# badge.net
KiCad netlist of a schematic drawn in EAGLE
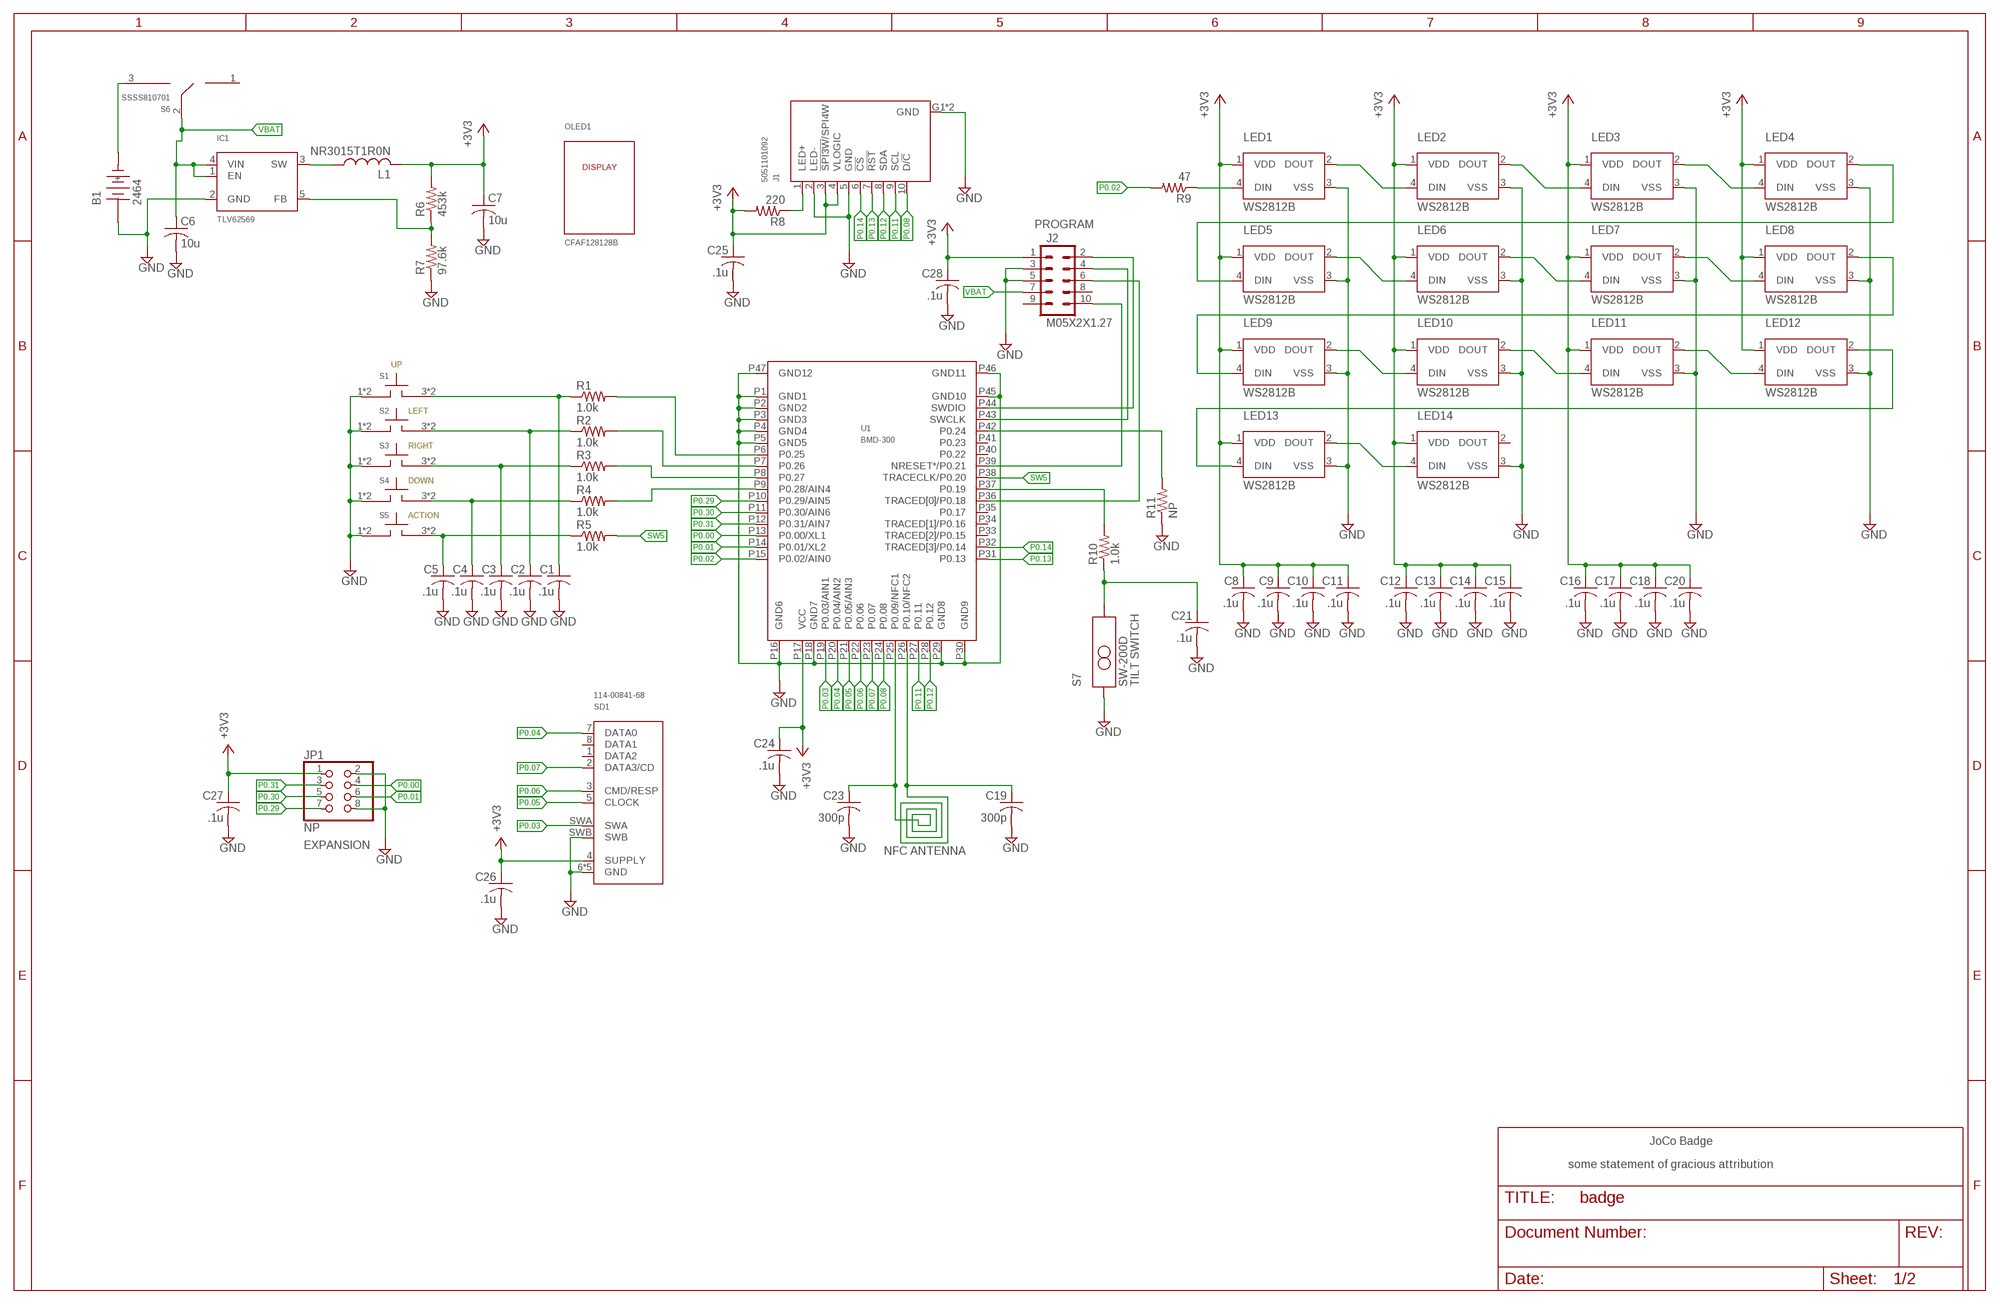
[diagram p0: schematic, sheet 1]
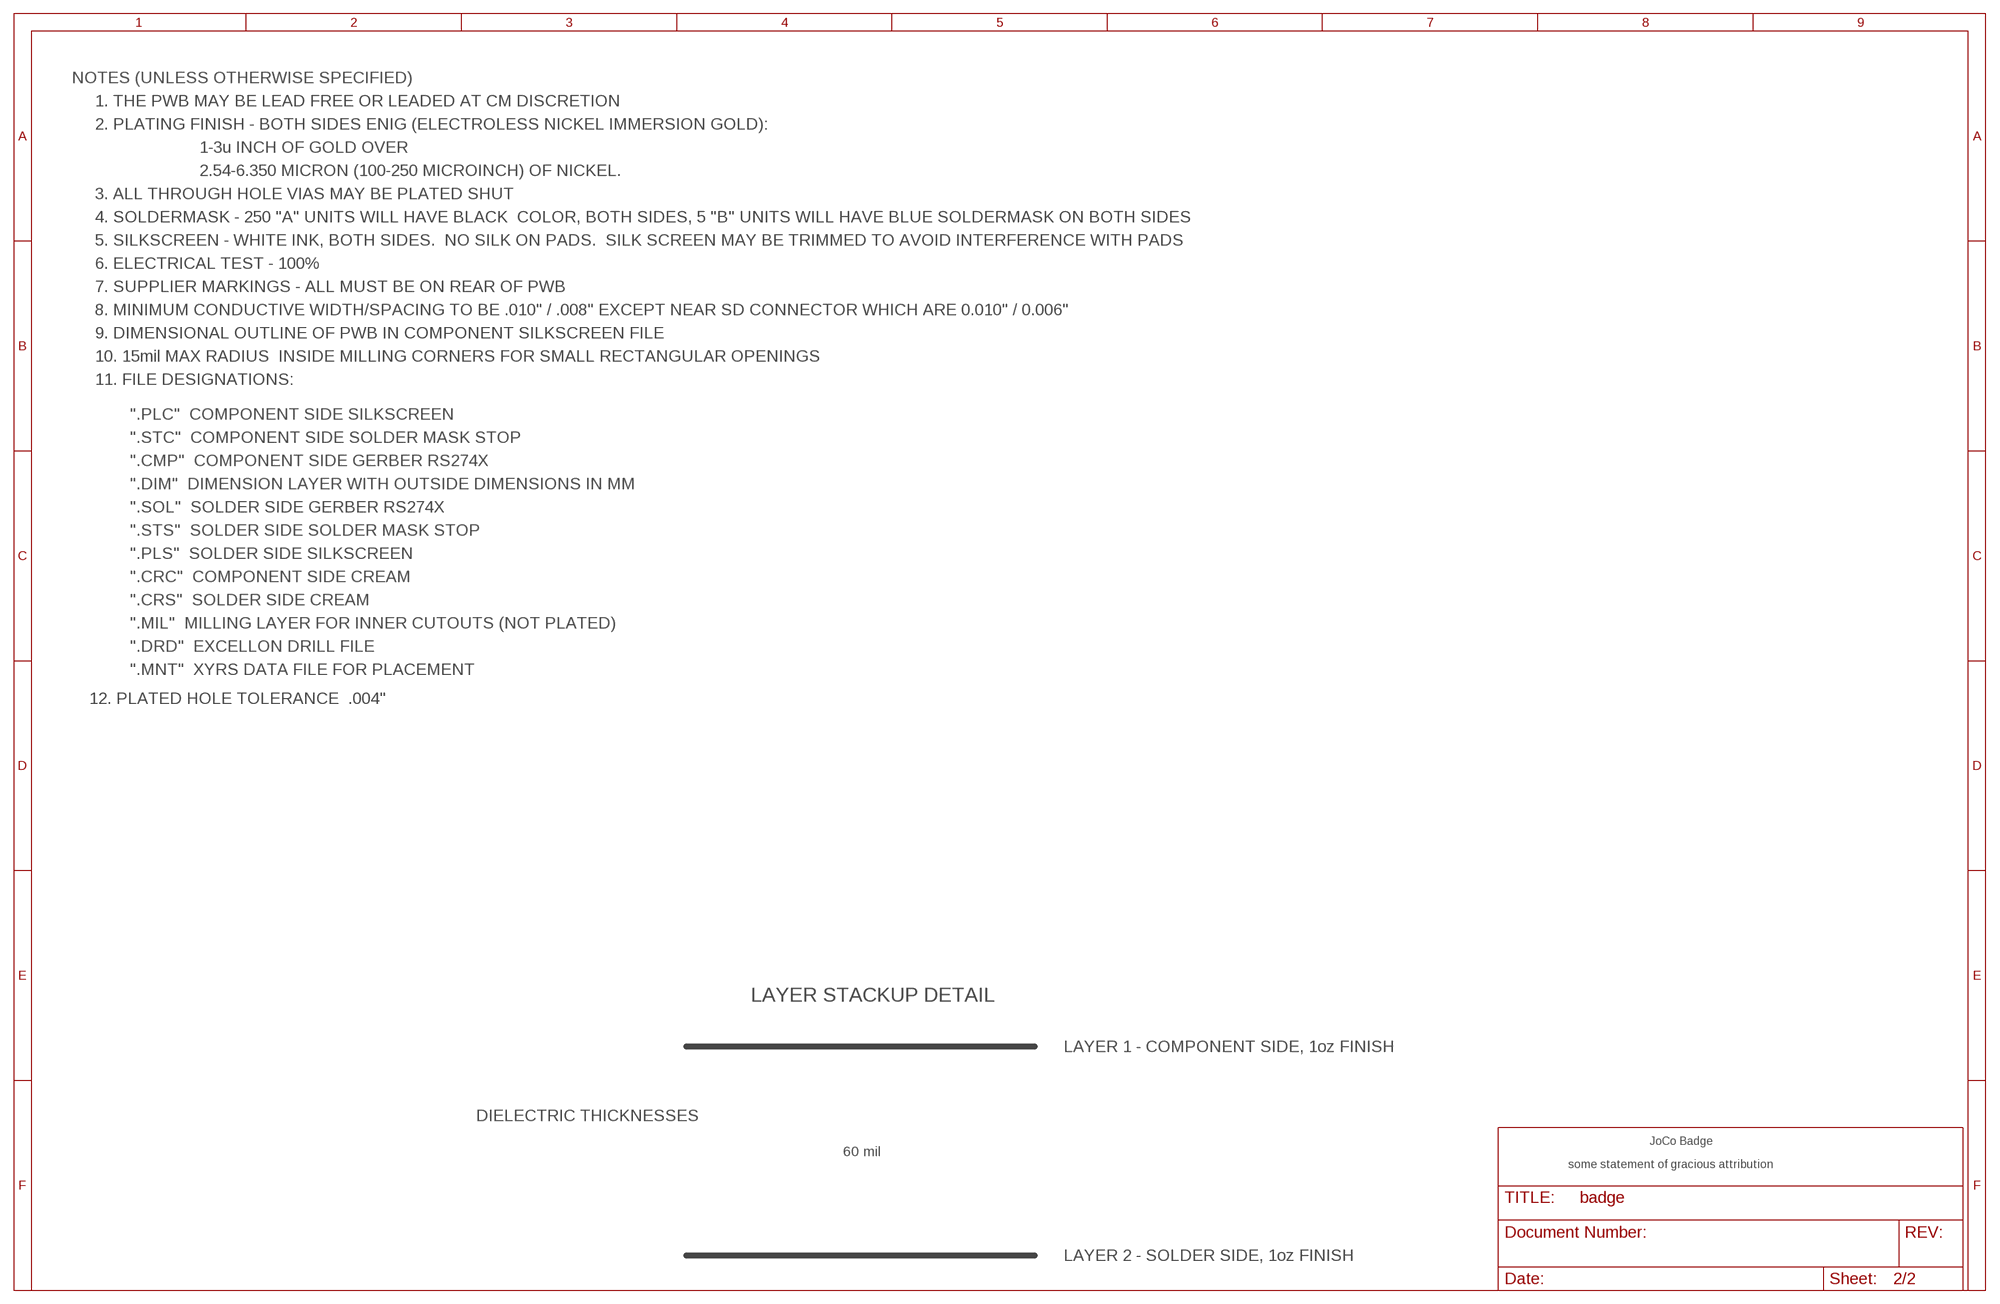
[diagram p1: schematic, sheet 2]

(export (version "E")
  (design (tool "Eeschema 10.0.6"))
  (components
    (comp (ref "B1")
      (value "2464")
      (footprint "eagle-import:2464")
      (libsource (lib "eagle-import") (part "2464"))
    )
    (comp (ref "C1")
      (value ".1u")
      (footprint "eagle-import:C0402K")
      (libsource (lib "eagle-import") (part "C-USC0402K"))
    )
    (comp (ref "C2")
      (value ".1u")
      (footprint "eagle-import:C0402K")
      (libsource (lib "eagle-import") (part "C-USC0402K"))
    )
    (comp (ref "C3")
      (value ".1u")
      (footprint "eagle-import:C0402K")
      (libsource (lib "eagle-import") (part "C-USC0402K"))
    )
    (comp (ref "C4")
      (value ".1u")
      (footprint "eagle-import:C0402K")
      (libsource (lib "eagle-import") (part "C-USC0402K"))
    )
    (comp (ref "C5")
      (value ".1u")
      (footprint "eagle-import:C0402K")
      (libsource (lib "eagle-import") (part "C-USC0402K"))
    )
    (comp (ref "C6")
      (value "10u")
      (footprint "eagle-import:C0805K")
      (fields (field (name "MPN") "JMK212BJ106KD-T"))
      (libsource (lib "eagle-import") (part "C-USC0805K"))
    )
    (comp (ref "C7")
      (value "10u")
      (footprint "eagle-import:C0805K")
      (fields (field (name "MPN") "JMK212BJ106KD-T"))
      (libsource (lib "eagle-import") (part "C-USC0805K"))
    )
    (comp (ref "C8")
      (value ".1u")
      (footprint "eagle-import:C0402K")
      (libsource (lib "eagle-import") (part "C-USC0402K"))
    )
    (comp (ref "C9")
      (value ".1u")
      (footprint "eagle-import:C0402K")
      (libsource (lib "eagle-import") (part "C-USC0402K"))
    )
    (comp (ref "C10")
      (value ".1u")
      (footprint "eagle-import:C0402K")
      (libsource (lib "eagle-import") (part "C-USC0402K"))
    )
    (comp (ref "C11")
      (value ".1u")
      (footprint "eagle-import:C0402K")
      (libsource (lib "eagle-import") (part "C-USC0402K"))
    )
    (comp (ref "C12")
      (value ".1u")
      (footprint "eagle-import:C0402K")
      (libsource (lib "eagle-import") (part "C-USC0402K"))
    )
    (comp (ref "C13")
      (value ".1u")
      (footprint "eagle-import:C0402K")
      (libsource (lib "eagle-import") (part "C-USC0402K"))
    )
    (comp (ref "C14")
      (value ".1u")
      (footprint "eagle-import:C0402K")
      (libsource (lib "eagle-import") (part "C-USC0402K"))
    )
    (comp (ref "C15")
      (value ".1u")
      (footprint "eagle-import:C0402K")
      (libsource (lib "eagle-import") (part "C-USC0402K"))
    )
    (comp (ref "C16")
      (value ".1u")
      (footprint "eagle-import:C0402K")
      (libsource (lib "eagle-import") (part "C-USC0402K"))
    )
    (comp (ref "C17")
      (value ".1u")
      (footprint "eagle-import:C0402K")
      (libsource (lib "eagle-import") (part "C-USC0402K"))
    )
    (comp (ref "C18")
      (value ".1u")
      (footprint "eagle-import:C0402K")
      (libsource (lib "eagle-import") (part "C-USC0402K"))
    )
    (comp (ref "C19")
      (value "300p")
      (footprint "eagle-import:C0603K")
      (libsource (lib "eagle-import") (part "C-USC0603K"))
    )
    (comp (ref "C20")
      (value ".1u")
      (footprint "eagle-import:C0402K")
      (libsource (lib "eagle-import") (part "C-USC0402K"))
    )
    (comp (ref "C21")
      (value ".1u")
      (footprint "eagle-import:C0402K")
      (libsource (lib "eagle-import") (part "C-USC0402K"))
    )
    (comp (ref "C23")
      (value "300p")
      (footprint "eagle-import:C0603K")
      (libsource (lib "eagle-import") (part "C-USC0603K"))
    )
    (comp (ref "C24")
      (value ".1u")
      (footprint "eagle-import:C0402K")
      (libsource (lib "eagle-import") (part "C-USC0402K"))
    )
    (comp (ref "C25")
      (value ".1u")
      (footprint "eagle-import:C0402K")
      (libsource (lib "eagle-import") (part "C-USC0402K"))
    )
    (comp (ref "C26")
      (value ".1u")
      (footprint "eagle-import:C0402K")
      (libsource (lib "eagle-import") (part "C-USC0402K"))
    )
    (comp (ref "C27")
      (value ".1u")
      (footprint "eagle-import:C0402K")
      (libsource (lib "eagle-import") (part "C-USC0402K"))
    )
    (comp (ref "C28")
      (value ".1u")
      (footprint "eagle-import:C0402K")
      (libsource (lib "eagle-import") (part "C-USC0402K"))
    )
    (comp (ref "IC1")
      (value "TLV62569")
      (footprint "eagle-import:DBV-5")
      (libsource (lib "eagle-import") (part "TLV62569"))
    )
    (comp (ref "J1")
      (value "5051101092")
      (footprint "eagle-import:5051101092")
      (libsource (lib "eagle-import") (part "5051101092"))
    )
    (comp (ref "J2")
      (value "M05X2X1.27")
      (footprint "eagle-import:2X5X1.27")
      (libsource (lib "eagle-import") (part "M05X2X1.27"))
    )
    (comp (ref "JP1")
      (value "NP")
      (footprint "eagle-import:2X04")
      (libsource (lib "eagle-import") (part "PINHD-2X4"))
    )
    (comp (ref "L1")
      (value "NR3015T1R0N")
      (footprint "eagle-import:NR3015")
      (libsource (lib "eagle-import") (part "NR3015"))
    )
    (comp (ref "LED1")
      (value "WS2812B")
      (footprint "eagle-import:WS2812B")
      (libsource (lib "eagle-import") (part "WS2812B"))
    )
    (comp (ref "LED2")
      (value "WS2812B")
      (footprint "eagle-import:WS2812B")
      (libsource (lib "eagle-import") (part "WS2812B"))
    )
    (comp (ref "LED3")
      (value "WS2812B")
      (footprint "eagle-import:WS2812B")
      (libsource (lib "eagle-import") (part "WS2812B"))
    )
    (comp (ref "LED4")
      (value "WS2812B")
      (footprint "eagle-import:WS2812B")
      (libsource (lib "eagle-import") (part "WS2812B"))
    )
    (comp (ref "LED5")
      (value "WS2812B")
      (footprint "eagle-import:WS2812B")
      (libsource (lib "eagle-import") (part "WS2812B"))
    )
    (comp (ref "LED6")
      (value "WS2812B")
      (footprint "eagle-import:WS2812B")
      (libsource (lib "eagle-import") (part "WS2812B"))
    )
    (comp (ref "LED7")
      (value "WS2812B")
      (footprint "eagle-import:WS2812B")
      (libsource (lib "eagle-import") (part "WS2812B"))
    )
    (comp (ref "LED8")
      (value "WS2812B")
      (footprint "eagle-import:WS2812B")
      (libsource (lib "eagle-import") (part "WS2812B"))
    )
    (comp (ref "LED9")
      (value "WS2812B")
      (footprint "eagle-import:WS2812B")
      (libsource (lib "eagle-import") (part "WS2812B"))
    )
    (comp (ref "LED10")
      (value "WS2812B")
      (footprint "eagle-import:WS2812B")
      (libsource (lib "eagle-import") (part "WS2812B"))
    )
    (comp (ref "LED11")
      (value "WS2812B")
      (footprint "eagle-import:WS2812B")
      (libsource (lib "eagle-import") (part "WS2812B"))
    )
    (comp (ref "LED12")
      (value "WS2812B")
      (footprint "eagle-import:WS2812B")
      (libsource (lib "eagle-import") (part "WS2812B"))
    )
    (comp (ref "LED13")
      (value "WS2812B")
      (footprint "eagle-import:WS2812B")
      (libsource (lib "eagle-import") (part "WS2812B"))
    )
    (comp (ref "LED14")
      (value "WS2812B")
      (footprint "eagle-import:WS2812B")
      (libsource (lib "eagle-import") (part "WS2812B"))
    )
    (comp (ref "OLED1")
      (value "CFAF128128B")
      (footprint "eagle-import:CFAF128128B")
      (libsource (lib "eagle-import") (part "CFAF128128B"))
    )
    (comp (ref "R1")
      (value "1.0k")
      (footprint "eagle-import:R0603")
      (libsource (lib "eagle-import") (part "R-US_R0603"))
    )
    (comp (ref "R2")
      (value "1.0k")
      (footprint "eagle-import:R0603")
      (libsource (lib "eagle-import") (part "R-US_R0603"))
    )
    (comp (ref "R3")
      (value "1.0k")
      (footprint "eagle-import:R0603")
      (libsource (lib "eagle-import") (part "R-US_R0603"))
    )
    (comp (ref "R4")
      (value "1.0k")
      (footprint "eagle-import:R0603")
      (libsource (lib "eagle-import") (part "R-US_R0603"))
    )
    (comp (ref "R5")
      (value "1.0k")
      (footprint "eagle-import:R0603")
      (libsource (lib "eagle-import") (part "R-US_R0603"))
    )
    (comp (ref "R6")
      (value "453k")
      (footprint "eagle-import:R0603")
      (libsource (lib "eagle-import") (part "R-US_R0603"))
    )
    (comp (ref "R7")
      (value "97.6k")
      (footprint "eagle-import:R0603")
      (libsource (lib "eagle-import") (part "R-US_R0603"))
    )
    (comp (ref "R8")
      (value "220")
      (footprint "eagle-import:R0603")
      (libsource (lib "eagle-import") (part "R-US_R0603"))
    )
    (comp (ref "R9")
      (value "47")
      (footprint "eagle-import:R0603")
      (libsource (lib "eagle-import") (part "R-US_R0603"))
    )
    (comp (ref "R10")
      (value "1.0k")
      (footprint "eagle-import:R0603")
      (libsource (lib "eagle-import") (part "R-US_R0603"))
    )
    (comp (ref "R11")
      (value "NP")
      (footprint "eagle-import:R0805")
      (libsource (lib "eagle-import") (part "R-US_R0805"))
    )
    (comp (ref "S1")
      (value "PTS810")
      (footprint "eagle-import:PTS810")
      (libsource (lib "eagle-import") (part "PTS810"))
    )
    (comp (ref "S2")
      (value "PTS810")
      (footprint "eagle-import:PTS810")
      (libsource (lib "eagle-import") (part "PTS810"))
    )
    (comp (ref "S3")
      (value "PTS810")
      (footprint "eagle-import:PTS810")
      (libsource (lib "eagle-import") (part "PTS810"))
    )
    (comp (ref "S4")
      (value "PTS810")
      (footprint "eagle-import:PTS810")
      (libsource (lib "eagle-import") (part "PTS810"))
    )
    (comp (ref "S5")
      (value "PTS810")
      (footprint "eagle-import:PTS810")
      (libsource (lib "eagle-import") (part "PTS810"))
    )
    (comp (ref "S6")
      (value "SSSS810701")
      (footprint "eagle-import:SSSS810701")
      (libsource (lib "eagle-import") (part "SSSS810701"))
    )
    (comp (ref "S7")
      (value "SW-200D")
      (footprint "eagle-import:SW-200D")
      (libsource (lib "eagle-import") (part "SW-200D"))
    )
    (comp (ref "SD1")
      (value "114-00841-68")
      (footprint "eagle-import:114-00841-68")
      (libsource (lib "eagle-import") (part "114-00841-68"))
    )
    (comp (ref "U1")
      (value "BMD-300")
      (footprint "eagle-import:BMD-300")
      (libsource (lib "eagle-import") (part "BMD-300"))
    )
  )
  (nets
    (net (code "1") (name "+3V3") (class "Default")
      (node (ref "C10") (pin "1") (pinfunction "1_1") (pintype "passive"))
      (node (ref "C11") (pin "1") (pinfunction "1_1") (pintype "passive"))
      (node (ref "C12") (pin "1") (pinfunction "1_1") (pintype "passive"))
      (node (ref "C13") (pin "1") (pinfunction "1_1") (pintype "passive"))
      (node (ref "C14") (pin "1") (pinfunction "1_1") (pintype "passive"))
      (node (ref "C15") (pin "1") (pinfunction "1_1") (pintype "passive"))
      (node (ref "C16") (pin "1") (pinfunction "1_1") (pintype "passive"))
      (node (ref "C17") (pin "1") (pinfunction "1_1") (pintype "passive"))
      (node (ref "C18") (pin "1") (pinfunction "1_1") (pintype "passive"))
      (node (ref "C20") (pin "1") (pinfunction "1_1") (pintype "passive"))
      (node (ref "C24") (pin "1") (pinfunction "1_1") (pintype "passive"))
      (node (ref "C25") (pin "1") (pinfunction "1_1") (pintype "passive"))
      (node (ref "C26") (pin "1") (pinfunction "1_1") (pintype "passive"))
      (node (ref "C27") (pin "1") (pinfunction "1_1") (pintype "passive"))
      (node (ref "C28") (pin "1") (pinfunction "1_1") (pintype "passive"))
      (node (ref "C7") (pin "1") (pinfunction "1_1") (pintype "passive"))
      (node (ref "C8") (pin "1") (pinfunction "1_1") (pintype "passive"))
      (node (ref "C9") (pin "1") (pinfunction "1_1") (pintype "passive"))
      (node (ref "J1") (pin "3") (pinfunction "~{SPI3W}/SPI4W_3") (pintype "bidirectional"))
      (node (ref "J1") (pin "4") (pinfunction "VLOGIC_4") (pintype "bidirectional"))
      (node (ref "J2") (pin "1") (pinfunction "1_1") (pintype "passive"))
      (node (ref "JP1") (pin "1") (pinfunction "1_1") (pintype "passive"))
      (node (ref "L1") (pin "2") (pinfunction "2_2") (pintype "passive"))
      (node (ref "LED1") (pin "1") (pinfunction "VDD_1") (pintype "bidirectional"))
      (node (ref "LED10") (pin "1") (pinfunction "VDD_1") (pintype "bidirectional"))
      (node (ref "LED11") (pin "1") (pinfunction "VDD_1") (pintype "bidirectional"))
      (node (ref "LED12") (pin "1") (pinfunction "VDD_1") (pintype "bidirectional"))
      (node (ref "LED13") (pin "1") (pinfunction "VDD_1") (pintype "bidirectional"))
      (node (ref "LED14") (pin "1") (pinfunction "VDD_1") (pintype "bidirectional"))
      (node (ref "LED2") (pin "1") (pinfunction "VDD_1") (pintype "bidirectional"))
      (node (ref "LED3") (pin "1") (pinfunction "VDD_1") (pintype "bidirectional"))
      (node (ref "LED4") (pin "1") (pinfunction "VDD_1") (pintype "bidirectional"))
      (node (ref "LED5") (pin "1") (pinfunction "VDD_1") (pintype "bidirectional"))
      (node (ref "LED6") (pin "1") (pinfunction "VDD_1") (pintype "bidirectional"))
      (node (ref "LED7") (pin "1") (pinfunction "VDD_1") (pintype "bidirectional"))
      (node (ref "LED8") (pin "1") (pinfunction "VDD_1") (pintype "bidirectional"))
      (node (ref "LED9") (pin "1") (pinfunction "VDD_1") (pintype "bidirectional"))
      (node (ref "R6") (pin "2") (pinfunction "2_2") (pintype "passive"))
      (node (ref "R8") (pin "2") (pinfunction "2_2") (pintype "passive"))
      (node (ref "SD1") (pin "4") (pinfunction "SUPPLY_4") (pintype "bidirectional"))
      (node (ref "U1") (pin "P17") (pinfunction "VCC_P17") (pintype "bidirectional"))
    )
    (net (code "2") (name "GND") (class "Default")
      (node (ref "B1") (pin "-") (pinfunction "-_-") (pintype "bidirectional"))
      (node (ref "C1") (pin "2") (pinfunction "2_2") (pintype "passive"))
      (node (ref "C10") (pin "2") (pinfunction "2_2") (pintype "passive"))
      (node (ref "C11") (pin "2") (pinfunction "2_2") (pintype "passive"))
      (node (ref "C12") (pin "2") (pinfunction "2_2") (pintype "passive"))
      (node (ref "C13") (pin "2") (pinfunction "2_2") (pintype "passive"))
      (node (ref "C14") (pin "2") (pinfunction "2_2") (pintype "passive"))
      (node (ref "C15") (pin "2") (pinfunction "2_2") (pintype "passive"))
      (node (ref "C16") (pin "2") (pinfunction "2_2") (pintype "passive"))
      (node (ref "C17") (pin "2") (pinfunction "2_2") (pintype "passive"))
      (node (ref "C18") (pin "2") (pinfunction "2_2") (pintype "passive"))
      (node (ref "C19") (pin "2") (pinfunction "2_2") (pintype "passive"))
      (node (ref "C2") (pin "2") (pinfunction "2_2") (pintype "passive"))
      (node (ref "C20") (pin "2") (pinfunction "2_2") (pintype "passive"))
      (node (ref "C21") (pin "2") (pinfunction "2_2") (pintype "passive"))
      (node (ref "C23") (pin "2") (pinfunction "2_2") (pintype "passive"))
      (node (ref "C24") (pin "2") (pinfunction "2_2") (pintype "passive"))
      (node (ref "C25") (pin "2") (pinfunction "2_2") (pintype "passive"))
      (node (ref "C26") (pin "2") (pinfunction "2_2") (pintype "passive"))
      (node (ref "C27") (pin "2") (pinfunction "2_2") (pintype "passive"))
      (node (ref "C28") (pin "2") (pinfunction "2_2") (pintype "passive"))
      (node (ref "C3") (pin "2") (pinfunction "2_2") (pintype "passive"))
      (node (ref "C4") (pin "2") (pinfunction "2_2") (pintype "passive"))
      (node (ref "C5") (pin "2") (pinfunction "2_2") (pintype "passive"))
      (node (ref "C6") (pin "2") (pinfunction "2_2") (pintype "passive"))
      (node (ref "C7") (pin "2") (pinfunction "2_2") (pintype "passive"))
      (node (ref "C8") (pin "2") (pinfunction "2_2") (pintype "passive"))
      (node (ref "C9") (pin "2") (pinfunction "2_2") (pintype "passive"))
      (node (ref "IC1") (pin "2") (pinfunction "GND_2") (pintype "bidirectional"))
      (node (ref "J1") (pin "2") (pinfunction "LED-_2") (pintype "bidirectional"))
      (node (ref "J1") (pin "5") (pinfunction "GND_5") (pintype "bidirectional"))
      (node (ref "J1") (pin "G1") (pinfunction "GND_G1") (pintype "bidirectional"))
      (node (ref "J1") (pin "G2") (pinfunction "GND_G2") (pintype "bidirectional"))
      (node (ref "J2") (pin "3") (pinfunction "3_3") (pintype "passive"))
      (node (ref "J2") (pin "5") (pinfunction "5_5") (pintype "passive"))
      (node (ref "JP1") (pin "2") (pinfunction "2_2") (pintype "passive"))
      (node (ref "JP1") (pin "8") (pinfunction "8_8") (pintype "passive"))
      (node (ref "LED1") (pin "3") (pinfunction "VSS_3") (pintype "bidirectional"))
      (node (ref "LED10") (pin "3") (pinfunction "VSS_3") (pintype "bidirectional"))
      (node (ref "LED11") (pin "3") (pinfunction "VSS_3") (pintype "bidirectional"))
      (node (ref "LED12") (pin "3") (pinfunction "VSS_3") (pintype "bidirectional"))
      (node (ref "LED13") (pin "3") (pinfunction "VSS_3") (pintype "bidirectional"))
      (node (ref "LED14") (pin "3") (pinfunction "VSS_3") (pintype "bidirectional"))
      (node (ref "LED2") (pin "3") (pinfunction "VSS_3") (pintype "bidirectional"))
      (node (ref "LED3") (pin "3") (pinfunction "VSS_3") (pintype "bidirectional"))
      (node (ref "LED4") (pin "3") (pinfunction "VSS_3") (pintype "bidirectional"))
      (node (ref "LED5") (pin "3") (pinfunction "VSS_3") (pintype "bidirectional"))
      (node (ref "LED6") (pin "3") (pinfunction "VSS_3") (pintype "bidirectional"))
      (node (ref "LED7") (pin "3") (pinfunction "VSS_3") (pintype "bidirectional"))
      (node (ref "LED8") (pin "3") (pinfunction "VSS_3") (pintype "bidirectional"))
      (node (ref "LED9") (pin "3") (pinfunction "VSS_3") (pintype "bidirectional"))
      (node (ref "R11") (pin "1") (pinfunction "1_1") (pintype "passive"))
      (node (ref "R7") (pin "1") (pinfunction "1_1") (pintype "passive"))
      (node (ref "S1") (pin "1") (pinfunction "A_1") (pintype "bidirectional"))
      (node (ref "S1") (pin "2") (pinfunction "A_2") (pintype "bidirectional"))
      (node (ref "S2") (pin "1") (pinfunction "A_1") (pintype "bidirectional"))
      (node (ref "S2") (pin "2") (pinfunction "A_2") (pintype "bidirectional"))
      (node (ref "S3") (pin "1") (pinfunction "A_1") (pintype "bidirectional"))
      (node (ref "S3") (pin "2") (pinfunction "A_2") (pintype "bidirectional"))
      (node (ref "S4") (pin "1") (pinfunction "A_1") (pintype "bidirectional"))
      (node (ref "S4") (pin "2") (pinfunction "A_2") (pintype "bidirectional"))
      (node (ref "S5") (pin "1") (pinfunction "A_1") (pintype "bidirectional"))
      (node (ref "S5") (pin "2") (pinfunction "A_2") (pintype "bidirectional"))
      (node (ref "S7") (pin "A") (pinfunction "P$1_A") (pintype "bidirectional"))
      (node (ref "SD1") (pin "6") (pinfunction "GND_6") (pintype "bidirectional"))
      (node (ref "SD1") (pin "G1") (pinfunction "GND_G1") (pintype "bidirectional"))
      (node (ref "SD1") (pin "G2") (pinfunction "GND_G2") (pintype "bidirectional"))
      (node (ref "SD1") (pin "G3") (pinfunction "GND_G3") (pintype "bidirectional"))
      (node (ref "SD1") (pin "G4") (pinfunction "GND_G4") (pintype "bidirectional"))
      (node (ref "SD1") (pin "SWB") (pinfunction "SWB_SWB") (pintype "bidirectional"))
      (node (ref "U1") (pin "P1") (pinfunction "GND1_P1") (pintype "bidirectional"))
      (node (ref "U1") (pin "P16") (pinfunction "GND6_P16") (pintype "bidirectional"))
      (node (ref "U1") (pin "P18") (pinfunction "GND7_P18") (pintype "bidirectional"))
      (node (ref "U1") (pin "P2") (pinfunction "GND2_P2") (pintype "bidirectional"))
      (node (ref "U1") (pin "P29") (pinfunction "GND8_P29") (pintype "bidirectional"))
      (node (ref "U1") (pin "P3") (pinfunction "GND3_P3") (pintype "bidirectional"))
      (node (ref "U1") (pin "P30") (pinfunction "GND9_P30") (pintype "bidirectional"))
      (node (ref "U1") (pin "P4") (pinfunction "GND4_P4") (pintype "bidirectional"))
      (node (ref "U1") (pin "P45") (pinfunction "GND10_P45") (pintype "bidirectional"))
      (node (ref "U1") (pin "P46") (pinfunction "GND11_P46") (pintype "bidirectional"))
      (node (ref "U1") (pin "P47") (pinfunction "GND12_P47") (pintype "bidirectional"))
      (node (ref "U1") (pin "P5") (pinfunction "GND5_P5") (pintype "bidirectional"))
    )
    (net (code "3") (name "Net-(B1-Pad+)") (class "Default")
      (node (ref "B1") (pin "+") (pinfunction "+_+") (pintype "bidirectional"))
      (node (ref "S6") (pin "3") (pinfunction "3_3") (pintype "bidirectional"))
    )
    (net (code "4") (name "Net-(C1-Pad1)") (class "Default")
      (node (ref "C1") (pin "1") (pinfunction "1_1") (pintype "passive"))
      (node (ref "R1") (pin "1") (pinfunction "1_1") (pintype "passive"))
      (node (ref "S1") (pin "3") (pinfunction "B_3") (pintype "bidirectional"))
      (node (ref "S1") (pin "4") (pinfunction "B_4") (pintype "bidirectional"))
    )
    (net (code "5") (name "Net-(C2-Pad1)") (class "Default")
      (node (ref "C2") (pin "1") (pinfunction "1_1") (pintype "passive"))
      (node (ref "R2") (pin "1") (pinfunction "1_1") (pintype "passive"))
      (node (ref "S2") (pin "3") (pinfunction "B_3") (pintype "bidirectional"))
      (node (ref "S2") (pin "4") (pinfunction "B_4") (pintype "bidirectional"))
    )
    (net (code "6") (name "Net-(C3-Pad1)") (class "Default")
      (node (ref "C3") (pin "1") (pinfunction "1_1") (pintype "passive"))
      (node (ref "R3") (pin "1") (pinfunction "1_1") (pintype "passive"))
      (node (ref "S3") (pin "3") (pinfunction "B_3") (pintype "bidirectional"))
      (node (ref "S3") (pin "4") (pinfunction "B_4") (pintype "bidirectional"))
    )
    (net (code "7") (name "Net-(C4-Pad1)") (class "Default")
      (node (ref "C4") (pin "1") (pinfunction "1_1") (pintype "passive"))
      (node (ref "R4") (pin "1") (pinfunction "1_1") (pintype "passive"))
      (node (ref "S4") (pin "3") (pinfunction "B_3") (pintype "bidirectional"))
      (node (ref "S4") (pin "4") (pinfunction "B_4") (pintype "bidirectional"))
    )
    (net (code "8") (name "Net-(C5-Pad1)") (class "Default")
      (node (ref "C5") (pin "1") (pinfunction "1_1") (pintype "passive"))
      (node (ref "R5") (pin "1") (pinfunction "1_1") (pintype "passive"))
      (node (ref "S5") (pin "3") (pinfunction "B_3") (pintype "bidirectional"))
      (node (ref "S5") (pin "4") (pinfunction "B_4") (pintype "bidirectional"))
    )
    (net (code "9") (name "Net-(IC1-FB)") (class "Default")
      (node (ref "IC1") (pin "5") (pinfunction "FB_5") (pintype "bidirectional"))
      (node (ref "R6") (pin "1") (pinfunction "1_1") (pintype "passive"))
      (node (ref "R7") (pin "2") (pinfunction "2_2") (pintype "passive"))
    )
    (net (code "10") (name "Net-(IC1-SW)") (class "Default")
      (node (ref "IC1") (pin "3") (pinfunction "SW_3") (pintype "bidirectional"))
      (node (ref "L1") (pin "1") (pinfunction "1_1") (pintype "passive"))
    )
    (net (code "11") (name "Net-(J1-LED+)") (class "Default")
      (node (ref "J1") (pin "1") (pinfunction "LED+_1") (pintype "bidirectional"))
      (node (ref "R8") (pin "1") (pinfunction "1_1") (pintype "passive"))
    )
    (net (code "12") (name "Net-(LED1-DIN)") (class "Default")
      (node (ref "LED1") (pin "4") (pinfunction "DIN_4") (pintype "bidirectional"))
      (node (ref "R9") (pin "1") (pinfunction "1_1") (pintype "passive"))
    )
    (net (code "13") (name "Net-(LED1-DOUT)") (class "Default")
      (node (ref "LED1") (pin "2") (pinfunction "DOUT_2") (pintype "bidirectional"))
      (node (ref "LED2") (pin "4") (pinfunction "DIN_4") (pintype "bidirectional"))
    )
    (net (code "14") (name "Net-(LED2-DOUT)") (class "Default")
      (node (ref "LED2") (pin "2") (pinfunction "DOUT_2") (pintype "bidirectional"))
      (node (ref "LED3") (pin "4") (pinfunction "DIN_4") (pintype "bidirectional"))
    )
    (net (code "15") (name "Net-(LED3-DOUT)") (class "Default")
      (node (ref "LED3") (pin "2") (pinfunction "DOUT_2") (pintype "bidirectional"))
      (node (ref "LED4") (pin "4") (pinfunction "DIN_4") (pintype "bidirectional"))
    )
    (net (code "16") (name "Net-(LED4-DOUT)") (class "Default")
      (node (ref "LED4") (pin "2") (pinfunction "DOUT_2") (pintype "bidirectional"))
      (node (ref "LED5") (pin "4") (pinfunction "DIN_4") (pintype "bidirectional"))
    )
    (net (code "17") (name "Net-(LED5-DOUT)") (class "Default")
      (node (ref "LED5") (pin "2") (pinfunction "DOUT_2") (pintype "bidirectional"))
      (node (ref "LED6") (pin "4") (pinfunction "DIN_4") (pintype "bidirectional"))
    )
    (net (code "18") (name "Net-(LED6-DOUT)") (class "Default")
      (node (ref "LED6") (pin "2") (pinfunction "DOUT_2") (pintype "bidirectional"))
      (node (ref "LED7") (pin "4") (pinfunction "DIN_4") (pintype "bidirectional"))
    )
    (net (code "19") (name "Net-(LED7-DOUT)") (class "Default")
      (node (ref "LED7") (pin "2") (pinfunction "DOUT_2") (pintype "bidirectional"))
      (node (ref "LED8") (pin "4") (pinfunction "DIN_4") (pintype "bidirectional"))
    )
    (net (code "20") (name "Net-(LED8-DOUT)") (class "Default")
      (node (ref "LED8") (pin "2") (pinfunction "DOUT_2") (pintype "bidirectional"))
      (node (ref "LED9") (pin "4") (pinfunction "DIN_4") (pintype "bidirectional"))
    )
    (net (code "21") (name "Net-(LED10-DIN)") (class "Default")
      (node (ref "LED10") (pin "4") (pinfunction "DIN_4") (pintype "bidirectional"))
      (node (ref "LED9") (pin "2") (pinfunction "DOUT_2") (pintype "bidirectional"))
    )
    (net (code "22") (name "Net-(LED10-DOUT)") (class "Default")
      (node (ref "LED10") (pin "2") (pinfunction "DOUT_2") (pintype "bidirectional"))
      (node (ref "LED11") (pin "4") (pinfunction "DIN_4") (pintype "bidirectional"))
    )
    (net (code "23") (name "Net-(LED11-DOUT)") (class "Default")
      (node (ref "LED11") (pin "2") (pinfunction "DOUT_2") (pintype "bidirectional"))
      (node (ref "LED12") (pin "4") (pinfunction "DIN_4") (pintype "bidirectional"))
    )
    (net (code "24") (name "Net-(LED12-DOUT)") (class "Default")
      (node (ref "LED12") (pin "2") (pinfunction "DOUT_2") (pintype "bidirectional"))
      (node (ref "LED13") (pin "4") (pinfunction "DIN_4") (pintype "bidirectional"))
    )
    (net (code "25") (name "Net-(LED13-DOUT)") (class "Default")
      (node (ref "LED13") (pin "2") (pinfunction "DOUT_2") (pintype "bidirectional"))
      (node (ref "LED14") (pin "4") (pinfunction "DIN_4") (pintype "bidirectional"))
    )
    (net (code "26") (name "Net-(S7-P$2)") (class "Default")
      (node (ref "C21") (pin "1") (pinfunction "1_1") (pintype "passive"))
      (node (ref "R10") (pin "1") (pinfunction "1_1") (pintype "passive"))
      (node (ref "S7") (pin "C") (pinfunction "P$2_C") (pintype "bidirectional"))
    )
    (net (code "27") (name "Net-(U1-NRESET*{slash}P0.21)") (class "Default")
      (node (ref "J2") (pin "10") (pinfunction "10_10") (pintype "passive"))
      (node (ref "U1") (pin "P39") (pinfunction "NRESET*/P0.21_P39") (pintype "bidirectional"))
    )
    (net (code "28") (name "Net-(U1-P0.09{slash}NFC1)") (class "Default")
      (node (ref "C19") (pin "1") (pinfunction "1_1") (pintype "passive"))
      (node (ref "C23") (pin "1") (pinfunction "1_1") (pintype "passive"))
      (node (ref "U1") (pin "P25") (pinfunction "P0.09/NFC1_P25") (pintype "bidirectional"))
      (node (ref "U1") (pin "P26") (pinfunction "P0.10/NFC2_P26") (pintype "bidirectional"))
    )
    (net (code "29") (name "Net-(U1-P0.19)") (class "Default")
      (node (ref "R10") (pin "2") (pinfunction "2_2") (pintype "passive"))
      (node (ref "U1") (pin "P37") (pinfunction "P0.19_P37") (pintype "bidirectional"))
    )
    (net (code "30") (name "Net-(U1-P0.24)") (class "Default")
      (node (ref "R11") (pin "2") (pinfunction "2_2") (pintype "passive"))
      (node (ref "U1") (pin "P42") (pinfunction "P0.24_P42") (pintype "bidirectional"))
    )
    (net (code "31") (name "Net-(U1-P0.25)") (class "Default")
      (node (ref "R1") (pin "2") (pinfunction "2_2") (pintype "passive"))
      (node (ref "U1") (pin "P6") (pinfunction "P0.25_P6") (pintype "bidirectional"))
    )
    (net (code "32") (name "Net-(U1-P0.26)") (class "Default")
      (node (ref "R2") (pin "2") (pinfunction "2_2") (pintype "passive"))
      (node (ref "U1") (pin "P7") (pinfunction "P0.26_P7") (pintype "bidirectional"))
    )
    (net (code "33") (name "Net-(U1-P0.27)") (class "Default")
      (node (ref "R3") (pin "2") (pinfunction "2_2") (pintype "passive"))
      (node (ref "U1") (pin "P8") (pinfunction "P0.27_P8") (pintype "bidirectional"))
    )
    (net (code "34") (name "Net-(U1-P0.28{slash}AIN4)") (class "Default")
      (node (ref "R4") (pin "2") (pinfunction "2_2") (pintype "passive"))
      (node (ref "U1") (pin "P9") (pinfunction "P0.28/AIN4_P9") (pintype "bidirectional"))
    )
    (net (code "35") (name "Net-(U1-SWCLK)") (class "Default")
      (node (ref "J2") (pin "4") (pinfunction "4_4") (pintype "passive"))
      (node (ref "U1") (pin "P43") (pinfunction "SWCLK_P43") (pintype "bidirectional"))
    )
    (net (code "36") (name "Net-(U1-SWDIO)") (class "Default")
      (node (ref "J2") (pin "2") (pinfunction "2_2") (pintype "passive"))
      (node (ref "U1") (pin "P44") (pinfunction "SWDIO_P44") (pintype "bidirectional"))
    )
    (net (code "37") (name "Net-(U1-TRACED[0]{slash}P0.18)") (class "Default")
      (node (ref "J2") (pin "6") (pinfunction "6_6") (pintype "passive"))
      (node (ref "U1") (pin "P36") (pinfunction "TRACED[0]/P0.18_P36") (pintype "bidirectional"))
    )
    (net (code "38") (name "P0.00") (class "Default")
      (node (ref "JP1") (pin "4") (pinfunction "4_4") (pintype "passive"))
      (node (ref "U1") (pin "P13") (pinfunction "P0.00/XL1_P13") (pintype "bidirectional"))
    )
    (net (code "39") (name "P0.01") (class "Default")
      (node (ref "JP1") (pin "6") (pinfunction "6_6") (pintype "passive"))
      (node (ref "U1") (pin "P14") (pinfunction "P0.01/XL2_P14") (pintype "bidirectional"))
    )
    (net (code "40") (name "P0.02") (class "Default")
      (node (ref "R9") (pin "2") (pinfunction "2_2") (pintype "passive"))
      (node (ref "U1") (pin "P15") (pinfunction "P0.02/AIN0_P15") (pintype "bidirectional"))
    )
    (net (code "41") (name "P0.03") (class "Default")
      (node (ref "SD1") (pin "SWA") (pinfunction "SWA_SWA") (pintype "bidirectional"))
      (node (ref "U1") (pin "P19") (pinfunction "P0.03/AIN1_P19") (pintype "bidirectional"))
    )
    (net (code "42") (name "P0.04") (class "Default")
      (node (ref "SD1") (pin "7") (pinfunction "DATA0_7") (pintype "bidirectional"))
      (node (ref "U1") (pin "P20") (pinfunction "P0.04/AIN2_P20") (pintype "bidirectional"))
    )
    (net (code "43") (name "P0.05") (class "Default")
      (node (ref "SD1") (pin "5") (pinfunction "CLOCK_5") (pintype "bidirectional"))
      (node (ref "U1") (pin "P21") (pinfunction "P0.05/AIN3_P21") (pintype "bidirectional"))
    )
    (net (code "44") (name "P0.06") (class "Default")
      (node (ref "SD1") (pin "3") (pinfunction "CMD/RESP_3") (pintype "bidirectional"))
      (node (ref "U1") (pin "P22") (pinfunction "P0.06_P22") (pintype "bidirectional"))
    )
    (net (code "45") (name "P0.07") (class "Default")
      (node (ref "SD1") (pin "2") (pinfunction "DATA3/CD_2") (pintype "bidirectional"))
      (node (ref "U1") (pin "P23") (pinfunction "P0.07_P23") (pintype "bidirectional"))
    )
    (net (code "46") (name "P0.08") (class "Default")
      (node (ref "J1") (pin "10") (pinfunction "D/~{C}_10") (pintype "bidirectional"))
      (node (ref "U1") (pin "P24") (pinfunction "P0.08_P24") (pintype "bidirectional"))
    )
    (net (code "47") (name "P0.11") (class "Default")
      (node (ref "J1") (pin "9") (pinfunction "SCL_9") (pintype "bidirectional"))
      (node (ref "U1") (pin "P27") (pinfunction "P0.11_P27") (pintype "bidirectional"))
    )
    (net (code "48") (name "P0.12") (class "Default")
      (node (ref "J1") (pin "8") (pinfunction "SDA_8") (pintype "bidirectional"))
      (node (ref "U1") (pin "P28") (pinfunction "P0.12_P28") (pintype "bidirectional"))
    )
    (net (code "49") (name "P0.13") (class "Default")
      (node (ref "J1") (pin "7") (pinfunction "~{RST}_7") (pintype "bidirectional"))
      (node (ref "U1") (pin "P31") (pinfunction "P0.13_P31") (pintype "bidirectional"))
    )
    (net (code "50") (name "P0.14") (class "Default")
      (node (ref "J1") (pin "6") (pinfunction "~{CS}_6") (pintype "bidirectional"))
      (node (ref "U1") (pin "P32") (pinfunction "TRACED[3]/P0.14_P32") (pintype "bidirectional"))
    )
    (net (code "51") (name "P0.29") (class "Default")
      (node (ref "JP1") (pin "7") (pinfunction "7_7") (pintype "passive"))
      (node (ref "U1") (pin "P10") (pinfunction "P0.29/AIN5_P10") (pintype "bidirectional"))
    )
    (net (code "52") (name "P0.30") (class "Default")
      (node (ref "JP1") (pin "5") (pinfunction "5_5") (pintype "passive"))
      (node (ref "U1") (pin "P11") (pinfunction "P0.30/AIN6_P11") (pintype "bidirectional"))
    )
    (net (code "53") (name "P0.31") (class "Default")
      (node (ref "JP1") (pin "3") (pinfunction "3_3") (pintype "passive"))
      (node (ref "U1") (pin "P12") (pinfunction "P0.31/AIN7_P12") (pintype "bidirectional"))
    )
    (net (code "54") (name "SW5") (class "Default")
      (node (ref "R5") (pin "2") (pinfunction "2_2") (pintype "passive"))
      (node (ref "U1") (pin "P38") (pinfunction "TRACECLK/P0.20_P38") (pintype "bidirectional"))
    )
    (net (code "55") (name "VBAT") (class "Default")
      (node (ref "C6") (pin "1") (pinfunction "1_1") (pintype "passive"))
      (node (ref "IC1") (pin "1") (pinfunction "EN_1") (pintype "bidirectional"))
      (node (ref "IC1") (pin "4") (pinfunction "VIN_4") (pintype "bidirectional"))
      (node (ref "J2") (pin "7") (pinfunction "7_7") (pintype "passive"))
      (node (ref "S6") (pin "2") (pinfunction "2_2") (pintype "bidirectional"))
    )
    (net (code "56") (name "unconnected-(J2-Pad8)") (class "Default")
      (node (ref "J2") (pin "8") (pinfunction "8_8") (pintype "passive"))
    )
    (net (code "57") (name "unconnected-(J2-Pad9)") (class "Default")
      (node (ref "J2") (pin "9") (pinfunction "9_9") (pintype "passive"))
    )
    (net (code "58") (name "unconnected-(LED14-DOUT-Pad2)") (class "Default")
      (node (ref "LED14") (pin "2") (pinfunction "DOUT_2") (pintype "bidirectional"))
    )
    (net (code "59") (name "unconnected-(S6-Pad1)") (class "Default")
      (node (ref "S6") (pin "1") (pinfunction "1_1") (pintype "bidirectional"))
    )
    (net (code "60") (name "unconnected-(SD1-DATA1-Pad8)") (class "Default")
      (node (ref "SD1") (pin "8") (pinfunction "DATA1_8") (pintype "bidirectional"))
    )
    (net (code "61") (name "unconnected-(SD1-DATA2-Pad1)") (class "Default")
      (node (ref "SD1") (pin "1") (pinfunction "DATA2_1") (pintype "bidirectional"))
    )
    (net (code "62") (name "unconnected-(U1-P0.17-PadP35)") (class "Default")
      (node (ref "U1") (pin "P35") (pinfunction "P0.17_P35") (pintype "bidirectional"))
    )
    (net (code "63") (name "unconnected-(U1-P0.22-PadP40)") (class "Default")
      (node (ref "U1") (pin "P40") (pinfunction "P0.22_P40") (pintype "bidirectional"))
    )
    (net (code "64") (name "unconnected-(U1-P0.23-PadP41)") (class "Default")
      (node (ref "U1") (pin "P41") (pinfunction "P0.23_P41") (pintype "bidirectional"))
    )
    (net (code "65") (name "unconnected-(U1-TRACED[1]{slash}P0.16-PadP34)") (class "Default")
      (node (ref "U1") (pin "P34") (pinfunction "TRACED[1]/P0.16_P34") (pintype "bidirectional"))
    )
    (net (code "66") (name "unconnected-(U1-TRACED[2]{slash}P0.15-PadP33)") (class "Default")
      (node (ref "U1") (pin "P33") (pinfunction "TRACED[2]/P0.15_P33") (pintype "bidirectional"))
    )
  )
)
